# Encoder.net
KiCad netlist of a schematic drawn in Altium Designer
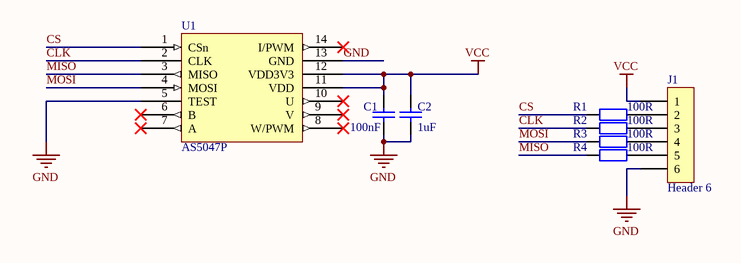
[diagram p0: Encoder.SchDoc]

(export (version "E")
  (design (tool "Eeschema 10.0.6"))
  (components
    (comp (ref "C1")
      (value "100nF")
      (footprint "0603C")
      (description "Capacitor")
      (fields (field (name "PUBLISHER") "Altium Limited"))
      (libsource (lib "prj-schlib") (part "Cap"))
    )
    (comp (ref "C2")
      (value "1uF")
      (footprint "0603C")
      (description "Capacitor")
      (fields (field (name "PUBLISHER") "Altium Limited"))
      (libsource (lib "prj-schlib") (part "Cap"))
    )
    (comp (ref "J1")
      (value "Header 6")
      (footprint "Pin HDR1X6/2.54mm-S")
      (libsource (lib "prj-schlib") (part "Header 6"))
    )
    (comp (ref "R1")
      (value "100R")
      (footprint "0603R")
      (description "Resistor")
      (fields (field (name "Comment") "Res2") (field (name "PUBLISHER") "Altium Limited"))
      (libsource (lib "prj-schlib") (part "Res2"))
    )
    (comp (ref "R2")
      (value "100R")
      (footprint "0603R")
      (description "Resistor")
      (fields (field (name "Comment") "Res2") (field (name "PUBLISHER") "Altium Limited"))
      (libsource (lib "prj-schlib") (part "Res2"))
    )
    (comp (ref "R3")
      (value "100R")
      (footprint "0603R")
      (description "Resistor")
      (fields (field (name "Comment") "Res2") (field (name "PUBLISHER") "Altium Limited"))
      (libsource (lib "prj-schlib") (part "Res2"))
    )
    (comp (ref "R4")
      (value "100R")
      (footprint "0603R")
      (description "Resistor")
      (fields (field (name "Comment") "Res2") (field (name "PUBLISHER") "Altium Limited"))
      (libsource (lib "prj-schlib") (part "Res2"))
    )
    (comp (ref "U1") (value "AS5047P") (footprint "TSSOP-14") (libsource (lib "prj-schlib") (part "AS5047P")))
  )
  (nets
    (net (code "1") (name "/CLK") (class "Default")
      (node (ref "R2") (pin "1") (pinfunction "1_1") (pintype "passive"))
      (node (ref "U1") (pin "2") (pinfunction "CLK_2") (pintype "passive"))
    )
    (net (code "2") (name "/CS") (class "Default")
      (node (ref "R1") (pin "1") (pinfunction "1_1") (pintype "passive"))
      (node (ref "U1") (pin "1") (pinfunction "CSn_1") (pintype "input"))
    )
    (net (code "3") (name "/MISO") (class "Default")
      (node (ref "R4") (pin "1") (pinfunction "1_1") (pintype "passive"))
      (node (ref "U1") (pin "3") (pinfunction "MISO_3") (pintype "output"))
    )
    (net (code "4") (name "/MOSI") (class "Default")
      (node (ref "R3") (pin "1") (pinfunction "1_1") (pintype "passive"))
      (node (ref "U1") (pin "4") (pinfunction "MOSI_4") (pintype "input"))
    )
    (net (code "5") (name "GND") (class "Default")
      (node (ref "C1") (pin "1") (pinfunction "1_1") (pintype "passive"))
      (node (ref "C2") (pin "1") (pinfunction "1_1") (pintype "passive"))
      (node (ref "J1") (pin "6") (pinfunction "6_6") (pintype "passive"))
      (node (ref "U1") (pin "13") (pinfunction "GND_13") (pintype "power_in"))
      (node (ref "U1") (pin "5") (pinfunction "TEST_5") (pintype "passive"))
    )
    (net (code "6") (name "Net-(J1-Pad2)") (class "Default")
      (node (ref "J1") (pin "2") (pinfunction "2_2") (pintype "passive"))
      (node (ref "R1") (pin "2") (pinfunction "2_2") (pintype "passive"))
    )
    (net (code "7") (name "Net-(J1-Pad3)") (class "Default")
      (node (ref "J1") (pin "3") (pinfunction "3_3") (pintype "passive"))
      (node (ref "R2") (pin "2") (pinfunction "2_2") (pintype "passive"))
    )
    (net (code "8") (name "Net-(J1-Pad4)") (class "Default")
      (node (ref "J1") (pin "4") (pinfunction "4_4") (pintype "passive"))
      (node (ref "R3") (pin "2") (pinfunction "2_2") (pintype "passive"))
    )
    (net (code "9") (name "Net-(J1-Pad5)") (class "Default")
      (node (ref "J1") (pin "5") (pinfunction "5_5") (pintype "passive"))
      (node (ref "R4") (pin "2") (pinfunction "2_2") (pintype "passive"))
    )
    (net (code "10") (name "VCC") (class "Default")
      (node (ref "C1") (pin "2") (pinfunction "2_2") (pintype "passive"))
      (node (ref "C2") (pin "2") (pinfunction "2_2") (pintype "passive"))
      (node (ref "J1") (pin "1") (pinfunction "1_1") (pintype "passive"))
      (node (ref "U1") (pin "11") (pinfunction "VDD_11") (pintype "power_in"))
      (node (ref "U1") (pin "12") (pinfunction "VDD3V3_12") (pintype "power_in"))
    )
    (net (code "11") (name "unconnected-(U1-A-Pad7)") (class "Default")
      (node (ref "U1") (pin "7") (pinfunction "A_7") (pintype "output+no_connect"))
    )
    (net (code "12") (name "unconnected-(U1-B-Pad6)") (class "Default")
      (node (ref "U1") (pin "6") (pinfunction "B_6") (pintype "output+no_connect"))
    )
    (net (code "13") (name "unconnected-(U1-I{slash}PWM-Pad14)") (class "Default")
      (node (ref "U1") (pin "14") (pinfunction "I/PWM_14") (pintype "output+no_connect"))
    )
    (net (code "14") (name "unconnected-(U1-U-Pad10)") (class "Default")
      (node (ref "U1") (pin "10") (pinfunction "U_10") (pintype "output+no_connect"))
    )
    (net (code "15") (name "unconnected-(U1-V-Pad9)") (class "Default")
      (node (ref "U1") (pin "9") (pinfunction "V_9") (pintype "output+no_connect"))
    )
    (net (code "16") (name "unconnected-(U1-W{slash}PWM-Pad8)") (class "Default")
      (node (ref "U1") (pin "8") (pinfunction "W/PWM_8") (pintype "output+no_connect"))
    )
  )
)
